# Connectors.net
KiCad netlist of a schematic drawn in Altium Designer
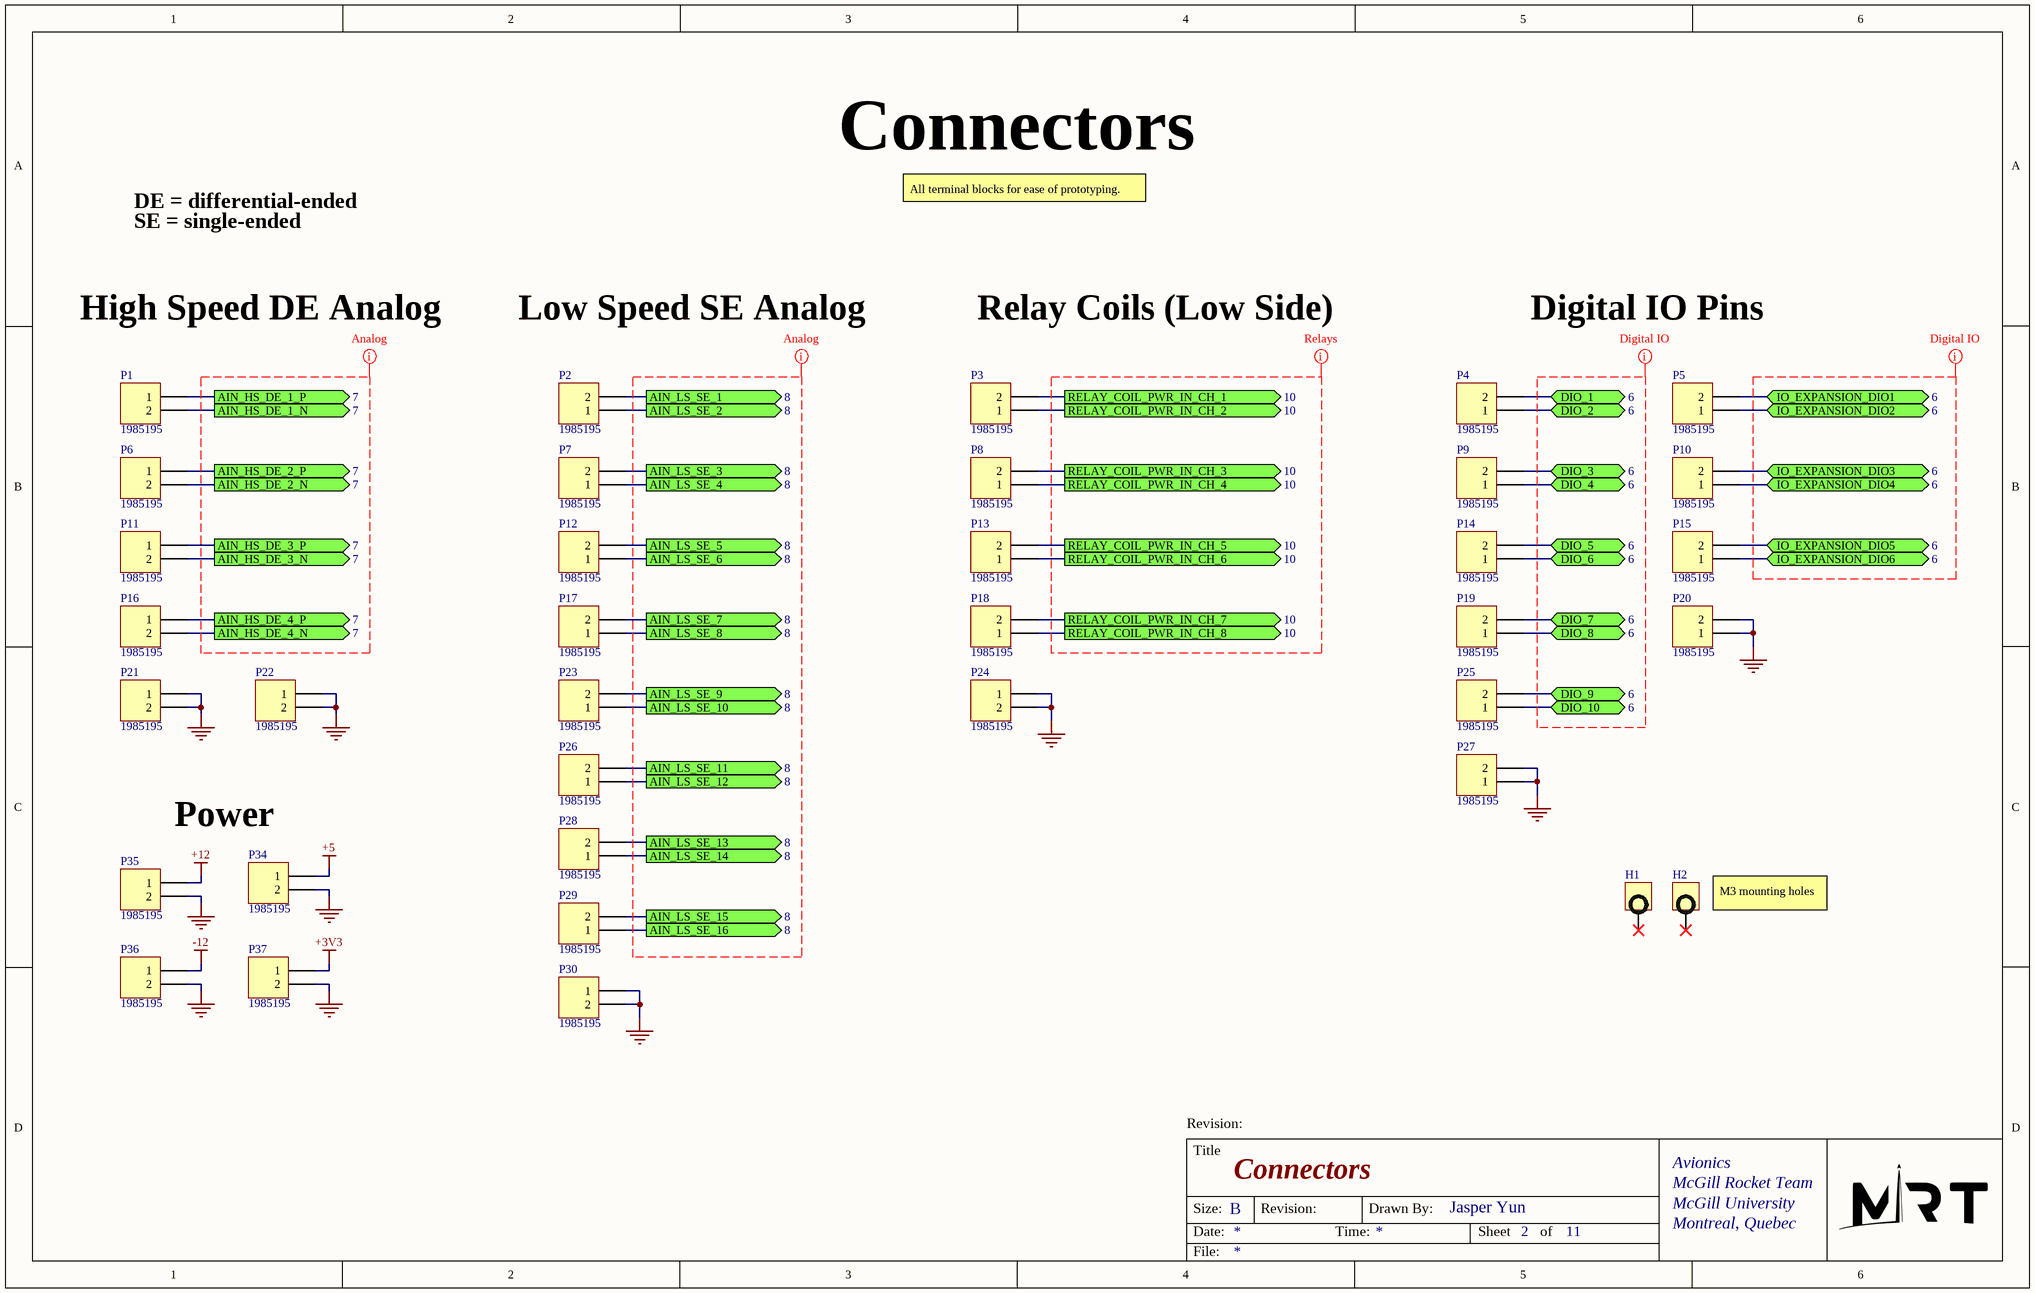
[diagram p0: Connectors.SchDoc]

(export (version "E")
  (design (tool "Eeschema 10.0.6"))
  (components
    (comp (ref "H1") (value "M3") (footprint "HOLE M3") (libsource (lib "MRT SCH Library") (part "Hole")))
    (comp (ref "H2") (value "M3") (footprint "HOLE M3") (libsource (lib "MRT SCH Library") (part "Hole")))
    (comp (ref "P1")
      (value "1985195")
      (footprint "Terminal Block 1985195 2-pos 3.5mm pitch")
      (description "Header, 2-Pin")
      (fields (field (name "PUBLISHER") "Altium Limited"))
      (libsource (lib "") (part "Header 2_1"))
    )
    (comp (ref "P2")
      (value "1985195")
      (footprint "Terminal Block 1985195 2-pos 3.5mm pitch")
      (description "Header, 2-Pin")
      (fields (field (name "PUBLISHER") "Altium Limited"))
      (libsource (lib "Miscellaneous Connectors") (part "Header 2"))
    )
    (comp (ref "P3")
      (value "1985195")
      (footprint "Terminal Block 1985195 2-pos 3.5mm pitch")
      (description "Header, 2-Pin")
      (fields (field (name "PUBLISHER") "Altium Limited"))
      (libsource (lib "Miscellaneous Connectors") (part "Header 2"))
    )
    (comp (ref "P4")
      (value "1985195")
      (footprint "Terminal Block 1985195 2-pos 3.5mm pitch")
      (description "Header, 2-Pin")
      (fields (field (name "PUBLISHER") "Altium Limited"))
      (libsource (lib "Miscellaneous Connectors") (part "Header 2"))
    )
    (comp (ref "P5")
      (value "1985195")
      (footprint "Terminal Block 1985195 2-pos 3.5mm pitch")
      (description "Header, 2-Pin")
      (fields (field (name "PUBLISHER") "Altium Limited"))
      (libsource (lib "Miscellaneous Connectors") (part "Header 2"))
    )
    (comp (ref "P6")
      (value "1985195")
      (footprint "Terminal Block 1985195 2-pos 3.5mm pitch")
      (description "Header, 2-Pin")
      (fields (field (name "PUBLISHER") "Altium Limited"))
      (libsource (lib "") (part "Header 2_1"))
    )
    (comp (ref "P7")
      (value "1985195")
      (footprint "Terminal Block 1985195 2-pos 3.5mm pitch")
      (description "Header, 2-Pin")
      (fields (field (name "PUBLISHER") "Altium Limited"))
      (libsource (lib "Miscellaneous Connectors") (part "Header 2"))
    )
    (comp (ref "P8")
      (value "1985195")
      (footprint "Terminal Block 1985195 2-pos 3.5mm pitch")
      (description "Header, 2-Pin")
      (fields (field (name "PUBLISHER") "Altium Limited"))
      (libsource (lib "Miscellaneous Connectors") (part "Header 2"))
    )
    (comp (ref "P9")
      (value "1985195")
      (footprint "Terminal Block 1985195 2-pos 3.5mm pitch")
      (description "Header, 2-Pin")
      (fields (field (name "PUBLISHER") "Altium Limited"))
      (libsource (lib "Miscellaneous Connectors") (part "Header 2"))
    )
    (comp (ref "P10")
      (value "1985195")
      (footprint "Terminal Block 1985195 2-pos 3.5mm pitch")
      (description "Header, 2-Pin")
      (fields (field (name "PUBLISHER") "Altium Limited"))
      (libsource (lib "Miscellaneous Connectors") (part "Header 2"))
    )
    (comp (ref "P11")
      (value "1985195")
      (footprint "Terminal Block 1985195 2-pos 3.5mm pitch")
      (description "Header, 2-Pin")
      (fields (field (name "PUBLISHER") "Altium Limited"))
      (libsource (lib "") (part "Header 2_1"))
    )
    (comp (ref "P12")
      (value "1985195")
      (footprint "Terminal Block 1985195 2-pos 3.5mm pitch")
      (description "Header, 2-Pin")
      (fields (field (name "PUBLISHER") "Altium Limited"))
      (libsource (lib "Miscellaneous Connectors") (part "Header 2"))
    )
    (comp (ref "P13")
      (value "1985195")
      (footprint "Terminal Block 1985195 2-pos 3.5mm pitch")
      (description "Header, 2-Pin")
      (fields (field (name "PUBLISHER") "Altium Limited"))
      (libsource (lib "Miscellaneous Connectors") (part "Header 2"))
    )
    (comp (ref "P14")
      (value "1985195")
      (footprint "Terminal Block 1985195 2-pos 3.5mm pitch")
      (description "Header, 2-Pin")
      (fields (field (name "PUBLISHER") "Altium Limited"))
      (libsource (lib "Miscellaneous Connectors") (part "Header 2"))
    )
    (comp (ref "P15")
      (value "1985195")
      (footprint "Terminal Block 1985195 2-pos 3.5mm pitch")
      (description "Header, 2-Pin")
      (fields (field (name "PUBLISHER") "Altium Limited"))
      (libsource (lib "Miscellaneous Connectors") (part "Header 2"))
    )
    (comp (ref "P16")
      (value "1985195")
      (footprint "Terminal Block 1985195 2-pos 3.5mm pitch")
      (description "Header, 2-Pin")
      (fields (field (name "PUBLISHER") "Altium Limited"))
      (libsource (lib "") (part "Header 2_1"))
    )
    (comp (ref "P17")
      (value "1985195")
      (footprint "Terminal Block 1985195 2-pos 3.5mm pitch")
      (description "Header, 2-Pin")
      (fields (field (name "PUBLISHER") "Altium Limited"))
      (libsource (lib "Miscellaneous Connectors") (part "Header 2"))
    )
    (comp (ref "P18")
      (value "1985195")
      (footprint "Terminal Block 1985195 2-pos 3.5mm pitch")
      (description "Header, 2-Pin")
      (fields (field (name "PUBLISHER") "Altium Limited"))
      (libsource (lib "Miscellaneous Connectors") (part "Header 2"))
    )
    (comp (ref "P19")
      (value "1985195")
      (footprint "Terminal Block 1985195 2-pos 3.5mm pitch")
      (description "Header, 2-Pin")
      (fields (field (name "PUBLISHER") "Altium Limited"))
      (libsource (lib "Miscellaneous Connectors") (part "Header 2"))
    )
    (comp (ref "P20")
      (value "1985195")
      (footprint "Terminal Block 1985195 2-pos 3.5mm pitch")
      (description "Header, 2-Pin")
      (fields (field (name "PUBLISHER") "Altium Limited"))
      (libsource (lib "Miscellaneous Connectors") (part "Header 2"))
    )
    (comp (ref "P21")
      (value "1985195")
      (footprint "Terminal Block 1985195 2-pos 3.5mm pitch")
      (description "Header, 2-Pin")
      (fields (field (name "PUBLISHER") "Altium Limited"))
      (libsource (lib "") (part "Header 2_1"))
    )
    (comp (ref "P22")
      (value "1985195")
      (footprint "Terminal Block 1985195 2-pos 3.5mm pitch")
      (description "Header, 2-Pin")
      (fields (field (name "PUBLISHER") "Altium Limited"))
      (libsource (lib "") (part "Header 2_1"))
    )
    (comp (ref "P23")
      (value "1985195")
      (footprint "Terminal Block 1985195 2-pos 3.5mm pitch")
      (description "Header, 2-Pin")
      (fields (field (name "PUBLISHER") "Altium Limited"))
      (libsource (lib "Miscellaneous Connectors") (part "Header 2"))
    )
    (comp (ref "P24")
      (value "1985195")
      (footprint "Terminal Block 1985195 2-pos 3.5mm pitch")
      (description "Header, 2-Pin")
      (fields (field (name "PUBLISHER") "Altium Limited"))
      (libsource (lib "") (part "Header 2_1"))
    )
    (comp (ref "P25")
      (value "1985195")
      (footprint "Terminal Block 1985195 2-pos 3.5mm pitch")
      (description "Header, 2-Pin")
      (fields (field (name "PUBLISHER") "Altium Limited"))
      (libsource (lib "Miscellaneous Connectors") (part "Header 2"))
    )
    (comp (ref "P26")
      (value "1985195")
      (footprint "Terminal Block 1985195 2-pos 3.5mm pitch")
      (description "Header, 2-Pin")
      (fields (field (name "PUBLISHER") "Altium Limited"))
      (libsource (lib "Miscellaneous Connectors") (part "Header 2"))
    )
    (comp (ref "P27")
      (value "1985195")
      (footprint "Terminal Block 1985195 2-pos 3.5mm pitch")
      (description "Header, 2-Pin")
      (fields (field (name "PUBLISHER") "Altium Limited"))
      (libsource (lib "Miscellaneous Connectors") (part "Header 2"))
    )
    (comp (ref "P28")
      (value "1985195")
      (footprint "Terminal Block 1985195 2-pos 3.5mm pitch")
      (description "Header, 2-Pin")
      (fields (field (name "PUBLISHER") "Altium Limited"))
      (libsource (lib "Miscellaneous Connectors") (part "Header 2"))
    )
    (comp (ref "P29")
      (value "1985195")
      (footprint "Terminal Block 1985195 2-pos 3.5mm pitch")
      (description "Header, 2-Pin")
      (fields (field (name "PUBLISHER") "Altium Limited"))
      (libsource (lib "Miscellaneous Connectors") (part "Header 2"))
    )
    (comp (ref "P30")
      (value "1985195")
      (footprint "Terminal Block 1985195 2-pos 3.5mm pitch")
      (description "Header, 2-Pin")
      (fields (field (name "PUBLISHER") "Altium Limited"))
      (libsource (lib "") (part "Header 2_1"))
    )
    (comp (ref "P34")
      (value "1985195")
      (footprint "Terminal Block 1985195 2-pos 3.5mm pitch")
      (description "Header, 2-Pin")
      (fields (field (name "PUBLISHER") "Altium Limited"))
      (libsource (lib "") (part "Header 2_1"))
    )
    (comp (ref "P35")
      (value "1985195")
      (footprint "Terminal Block 1985195 2-pos 3.5mm pitch")
      (description "Header, 2-Pin")
      (fields (field (name "PUBLISHER") "Altium Limited"))
      (libsource (lib "") (part "Header 2_1"))
    )
    (comp (ref "P36")
      (value "1985195")
      (footprint "Terminal Block 1985195 2-pos 3.5mm pitch")
      (description "Header, 2-Pin")
      (fields (field (name "PUBLISHER") "Altium Limited"))
      (libsource (lib "") (part "Header 2_1"))
    )
    (comp (ref "P37")
      (value "1985195")
      (footprint "Terminal Block 1985195 2-pos 3.5mm pitch")
      (description "Header, 2-Pin")
      (fields (field (name "PUBLISHER") "Altium Limited"))
      (libsource (lib "") (part "Header 2_1"))
    )
  )
  (nets
    (net (code "1") (name "+3V3") (class "Default")
      (node (ref "P37") (pin "1") (pinfunction "1_1") (pintype "passive"))
    )
    (net (code "2") (name "+5") (class "Default")
      (node (ref "P34") (pin "1") (pinfunction "1_1") (pintype "passive"))
    )
    (net (code "3") (name "+12") (class "Default")
      (node (ref "P35") (pin "1") (pinfunction "1_1") (pintype "passive"))
    )
    (net (code "4") (name "-12") (class "Default")
      (node (ref "P36") (pin "1") (pinfunction "1_1") (pintype "passive"))
    )
    (net (code "5") (name "/AIN_HS_DE_1_N") (class "Default")
      (node (ref "P1") (pin "2") (pinfunction "2_2") (pintype "passive"))
    )
    (net (code "6") (name "/AIN_HS_DE_1_P") (class "Default")
      (node (ref "P1") (pin "1") (pinfunction "1_1") (pintype "passive"))
    )
    (net (code "7") (name "/AIN_HS_DE_2_N") (class "Default")
      (node (ref "P6") (pin "2") (pinfunction "2_2") (pintype "passive"))
    )
    (net (code "8") (name "/AIN_HS_DE_2_P") (class "Default")
      (node (ref "P6") (pin "1") (pinfunction "1_1") (pintype "passive"))
    )
    (net (code "9") (name "/AIN_HS_DE_3_N") (class "Default")
      (node (ref "P11") (pin "2") (pinfunction "2_2") (pintype "passive"))
    )
    (net (code "10") (name "/AIN_HS_DE_3_P") (class "Default")
      (node (ref "P11") (pin "1") (pinfunction "1_1") (pintype "passive"))
    )
    (net (code "11") (name "/AIN_HS_DE_4_N") (class "Default")
      (node (ref "P16") (pin "2") (pinfunction "2_2") (pintype "passive"))
    )
    (net (code "12") (name "/AIN_HS_DE_4_P") (class "Default")
      (node (ref "P16") (pin "1") (pinfunction "1_1") (pintype "passive"))
    )
    (net (code "13") (name "/AIN_LS_SE_1") (class "Default")
      (node (ref "P2") (pin "2") (pinfunction "2_2") (pintype "passive"))
    )
    (net (code "14") (name "/AIN_LS_SE_2") (class "Default")
      (node (ref "P2") (pin "1") (pinfunction "1_1") (pintype "passive"))
    )
    (net (code "15") (name "/AIN_LS_SE_3") (class "Default")
      (node (ref "P7") (pin "2") (pinfunction "2_2") (pintype "passive"))
    )
    (net (code "16") (name "/AIN_LS_SE_4") (class "Default")
      (node (ref "P7") (pin "1") (pinfunction "1_1") (pintype "passive"))
    )
    (net (code "17") (name "/AIN_LS_SE_5") (class "Default")
      (node (ref "P12") (pin "2") (pinfunction "2_2") (pintype "passive"))
    )
    (net (code "18") (name "/AIN_LS_SE_6") (class "Default")
      (node (ref "P12") (pin "1") (pinfunction "1_1") (pintype "passive"))
    )
    (net (code "19") (name "/AIN_LS_SE_7") (class "Default")
      (node (ref "P17") (pin "2") (pinfunction "2_2") (pintype "passive"))
    )
    (net (code "20") (name "/AIN_LS_SE_8") (class "Default")
      (node (ref "P17") (pin "1") (pinfunction "1_1") (pintype "passive"))
    )
    (net (code "21") (name "/AIN_LS_SE_9") (class "Default")
      (node (ref "P23") (pin "2") (pinfunction "2_2") (pintype "passive"))
    )
    (net (code "22") (name "/AIN_LS_SE_10") (class "Default")
      (node (ref "P23") (pin "1") (pinfunction "1_1") (pintype "passive"))
    )
    (net (code "23") (name "/AIN_LS_SE_11") (class "Default")
      (node (ref "P26") (pin "2") (pinfunction "2_2") (pintype "passive"))
    )
    (net (code "24") (name "/AIN_LS_SE_12") (class "Default")
      (node (ref "P26") (pin "1") (pinfunction "1_1") (pintype "passive"))
    )
    (net (code "25") (name "/AIN_LS_SE_13") (class "Default")
      (node (ref "P28") (pin "2") (pinfunction "2_2") (pintype "passive"))
    )
    (net (code "26") (name "/AIN_LS_SE_14") (class "Default")
      (node (ref "P28") (pin "1") (pinfunction "1_1") (pintype "passive"))
    )
    (net (code "27") (name "/AIN_LS_SE_15") (class "Default")
      (node (ref "P29") (pin "2") (pinfunction "2_2") (pintype "passive"))
    )
    (net (code "28") (name "/AIN_LS_SE_16") (class "Default")
      (node (ref "P29") (pin "1") (pinfunction "1_1") (pintype "passive"))
    )
    (net (code "29") (name "/DIO_1") (class "Default")
      (node (ref "P4") (pin "2") (pinfunction "2_2") (pintype "passive"))
    )
    (net (code "30") (name "/DIO_2") (class "Default")
      (node (ref "P4") (pin "1") (pinfunction "1_1") (pintype "passive"))
    )
    (net (code "31") (name "/DIO_3") (class "Default")
      (node (ref "P9") (pin "2") (pinfunction "2_2") (pintype "passive"))
    )
    (net (code "32") (name "/DIO_4") (class "Default")
      (node (ref "P9") (pin "1") (pinfunction "1_1") (pintype "passive"))
    )
    (net (code "33") (name "/DIO_5") (class "Default")
      (node (ref "P14") (pin "2") (pinfunction "2_2") (pintype "passive"))
    )
    (net (code "34") (name "/DIO_6") (class "Default")
      (node (ref "P14") (pin "1") (pinfunction "1_1") (pintype "passive"))
    )
    (net (code "35") (name "/DIO_7") (class "Default")
      (node (ref "P19") (pin "2") (pinfunction "2_2") (pintype "passive"))
    )
    (net (code "36") (name "/DIO_8") (class "Default")
      (node (ref "P19") (pin "1") (pinfunction "1_1") (pintype "passive"))
    )
    (net (code "37") (name "/DIO_9") (class "Default")
      (node (ref "P25") (pin "2") (pinfunction "2_2") (pintype "passive"))
    )
    (net (code "38") (name "/DIO_10") (class "Default")
      (node (ref "P25") (pin "1") (pinfunction "1_1") (pintype "passive"))
    )
    (net (code "39") (name "/IO_EXPANSION_DIO1") (class "Default")
      (node (ref "P5") (pin "2") (pinfunction "2_2") (pintype "passive"))
    )
    (net (code "40") (name "/IO_EXPANSION_DIO2") (class "Default")
      (node (ref "P5") (pin "1") (pinfunction "1_1") (pintype "passive"))
    )
    (net (code "41") (name "/IO_EXPANSION_DIO3") (class "Default")
      (node (ref "P10") (pin "2") (pinfunction "2_2") (pintype "passive"))
    )
    (net (code "42") (name "/IO_EXPANSION_DIO4") (class "Default")
      (node (ref "P10") (pin "1") (pinfunction "1_1") (pintype "passive"))
    )
    (net (code "43") (name "/IO_EXPANSION_DIO5") (class "Default")
      (node (ref "P15") (pin "2") (pinfunction "2_2") (pintype "passive"))
    )
    (net (code "44") (name "/IO_EXPANSION_DIO6") (class "Default")
      (node (ref "P15") (pin "1") (pinfunction "1_1") (pintype "passive"))
    )
    (net (code "45") (name "/RELAY_COIL_PWR_IN_CH_1") (class "Default")
      (node (ref "P3") (pin "2") (pinfunction "2_2") (pintype "passive"))
    )
    (net (code "46") (name "/RELAY_COIL_PWR_IN_CH_2") (class "Default")
      (node (ref "P3") (pin "1") (pinfunction "1_1") (pintype "passive"))
    )
    (net (code "47") (name "/RELAY_COIL_PWR_IN_CH_3") (class "Default")
      (node (ref "P8") (pin "2") (pinfunction "2_2") (pintype "passive"))
    )
    (net (code "48") (name "/RELAY_COIL_PWR_IN_CH_4") (class "Default")
      (node (ref "P8") (pin "1") (pinfunction "1_1") (pintype "passive"))
    )
    (net (code "49") (name "/RELAY_COIL_PWR_IN_CH_5") (class "Default")
      (node (ref "P13") (pin "2") (pinfunction "2_2") (pintype "passive"))
    )
    (net (code "50") (name "/RELAY_COIL_PWR_IN_CH_6") (class "Default")
      (node (ref "P13") (pin "1") (pinfunction "1_1") (pintype "passive"))
    )
    (net (code "51") (name "/RELAY_COIL_PWR_IN_CH_7") (class "Default")
      (node (ref "P18") (pin "2") (pinfunction "2_2") (pintype "passive"))
    )
    (net (code "52") (name "/RELAY_COIL_PWR_IN_CH_8") (class "Default")
      (node (ref "P18") (pin "1") (pinfunction "1_1") (pintype "passive"))
    )
    (net (code "53") (name "GND") (class "Default")
      (node (ref "P20") (pin "1") (pinfunction "1_1") (pintype "passive"))
      (node (ref "P20") (pin "2") (pinfunction "2_2") (pintype "passive"))
      (node (ref "P21") (pin "1") (pinfunction "1_1") (pintype "passive"))
      (node (ref "P21") (pin "2") (pinfunction "2_2") (pintype "passive"))
      (node (ref "P22") (pin "1") (pinfunction "1_1") (pintype "passive"))
      (node (ref "P22") (pin "2") (pinfunction "2_2") (pintype "passive"))
      (node (ref "P24") (pin "1") (pinfunction "1_1") (pintype "passive"))
      (node (ref "P24") (pin "2") (pinfunction "2_2") (pintype "passive"))
      (node (ref "P27") (pin "1") (pinfunction "1_1") (pintype "passive"))
      (node (ref "P27") (pin "2") (pinfunction "2_2") (pintype "passive"))
      (node (ref "P30") (pin "1") (pinfunction "1_1") (pintype "passive"))
      (node (ref "P30") (pin "2") (pinfunction "2_2") (pintype "passive"))
      (node (ref "P34") (pin "2") (pinfunction "2_2") (pintype "passive"))
      (node (ref "P35") (pin "2") (pinfunction "2_2") (pintype "passive"))
      (node (ref "P36") (pin "2") (pinfunction "2_2") (pintype "passive"))
      (node (ref "P37") (pin "2") (pinfunction "2_2") (pintype "passive"))
    )
    (net (code "54") (name "unconnected-(H1-TERMINAL-Pad1)") (class "Default")
      (node (ref "H1") (pin "1") (pinfunction "TERMINAL_1") (pintype "passive+no_connect"))
    )
    (net (code "55") (name "unconnected-(H2-TERMINAL-Pad1)") (class "Default")
      (node (ref "H2") (pin "1") (pinfunction "TERMINAL_1") (pintype "passive+no_connect"))
    )
  )
)
